# dynamic_mic_preamp.net
KiCad netlist of a schematic drawn in EAGLE
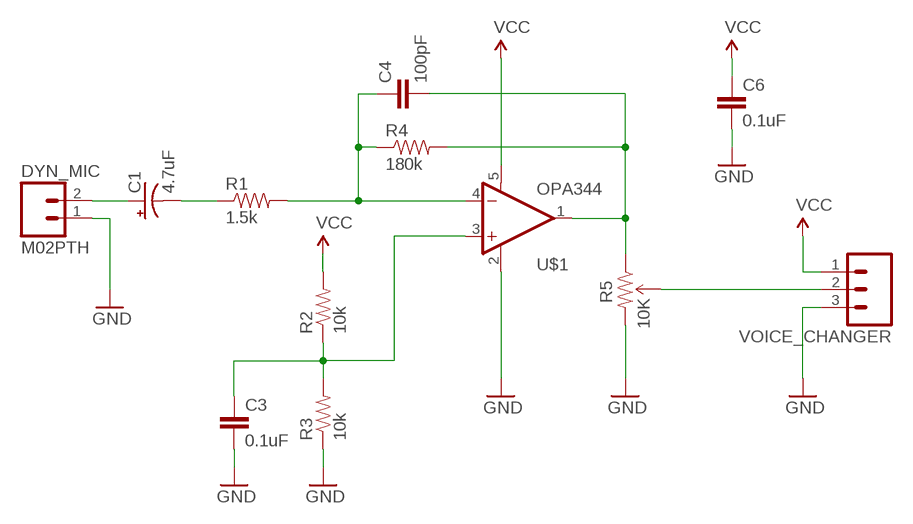
[diagram p0: schematic, sheet 1]

(export (version "E")
  (design (tool "Eeschema 10.0.6"))
  (components
    (comp (ref "C1")
      (value "4.7uF")
      (footprint "eagle-import:CPOL-RADIAL-100UF-25V")
      (libsource (lib "eagle-import") (part "CAP_POLPTH1"))
    )
    (comp (ref "C3")
      (value "0.1uF")
      (footprint "eagle-import:CAP-PTH-SMALL")
      (libsource (lib "eagle-import") (part "CAPPTH"))
    )
    (comp (ref "C4")
      (value "100pF")
      (footprint "eagle-import:CAP-PTH-SMALL")
      (libsource (lib "eagle-import") (part "CAPPTH"))
    )
    (comp (ref "C6")
      (value "0.1uF")
      (footprint "eagle-import:CAP-PTH-SMALL")
      (libsource (lib "eagle-import") (part "CAPPTH"))
    )
    (comp (ref "DYN_MIC")
      (value "M02PTH")
      (footprint "eagle-import:1X02")
      (libsource (lib "eagle-import") (part "M02PTH"))
    )
    (comp (ref "R1")
      (value "1.5k")
      (footprint "eagle-import:AXIAL-0.4")
      (libsource (lib "eagle-import") (part "RESISTORPTH-1/4W"))
    )
    (comp (ref "R2")
      (value "10k")
      (footprint "eagle-import:AXIAL-0.4")
      (libsource (lib "eagle-import") (part "RESISTORPTH-1/4W"))
    )
    (comp (ref "R3")
      (value "10k")
      (footprint "eagle-import:AXIAL-0.4")
      (libsource (lib "eagle-import") (part "RESISTORPTH-1/4W"))
    )
    (comp (ref "R4")
      (value "180k")
      (footprint "eagle-import:AXIAL-0.4")
      (libsource (lib "eagle-import") (part "RESISTORPTH-1/4W"))
    )
    (comp (ref "R5")
      (value "10K")
      (footprint "eagle-import:TRIMPOT-5MM-V2")
      (libsource (lib "eagle-import") (part "TRIMPOT"))
    )
    (comp (ref "U$1")
      (value "OPA344")
      (footprint "eagle-import:SOT23-5")
      (libsource (lib "eagle-import") (part "OPA344"))
    )
    (comp (ref "VOICE_CHANGER")
      (value "M03PTH")
      (footprint "eagle-import:1X03")
      (libsource (lib "eagle-import") (part "M03PTH"))
    )
  )
  (nets
    (net (code "1") (name "GND") (class "Default")
      (node (ref "C3") (pin "2") (pinfunction "2_2") (pintype "passive"))
      (node (ref "C6") (pin "2") (pinfunction "2_2") (pintype "passive"))
      (node (ref "DYN_MIC") (pin "1") (pinfunction "1_1") (pintype "passive"))
      (node (ref "R3") (pin "P$1") (pinfunction "1_P$1") (pintype "passive"))
      (node (ref "R5") (pin "C") (pinfunction "CW_C") (pintype "passive"))
      (node (ref "U$1") (pin "2") (pinfunction "V-_2") (pintype "power_in"))
      (node (ref "VOICE_CHANGER") (pin "3") (pinfunction "3_3") (pintype "passive"))
    )
    (net (code "2") (name "Net-(C1-+)") (class "Default")
      (node (ref "C1") (pin "1") (pinfunction "+_1") (pintype "passive"))
      (node (ref "DYN_MIC") (pin "2") (pinfunction "2_2") (pintype "passive"))
    )
    (net (code "3") (name "Net-(C1--)") (class "Default")
      (node (ref "C1") (pin "2") (pinfunction "-_2") (pintype "passive"))
      (node (ref "R1") (pin "P$1") (pinfunction "1_P$1") (pintype "passive"))
    )
    (net (code "4") (name "Net-(R1-2)") (class "Default")
      (node (ref "C4") (pin "1") (pinfunction "1_1") (pintype "passive"))
      (node (ref "R1") (pin "P$2") (pinfunction "2_P$2") (pintype "passive"))
      (node (ref "R4") (pin "P$1") (pinfunction "1_P$1") (pintype "passive"))
      (node (ref "U$1") (pin "4") (pinfunction "-IN_4") (pintype "input"))
    )
    (net (code "5") (name "Net-(R2-1)") (class "Default")
      (node (ref "C3") (pin "1") (pinfunction "1_1") (pintype "passive"))
      (node (ref "R2") (pin "P$1") (pinfunction "1_P$1") (pintype "passive"))
      (node (ref "R3") (pin "P$2") (pinfunction "2_P$2") (pintype "passive"))
      (node (ref "U$1") (pin "3") (pinfunction "+IN_3") (pintype "input"))
    )
    (net (code "6") (name "Net-(R4-2)") (class "Default")
      (node (ref "C4") (pin "2") (pinfunction "2_2") (pintype "passive"))
      (node (ref "R4") (pin "P$2") (pinfunction "2_P$2") (pintype "passive"))
      (node (ref "R5") (pin "A") (pinfunction "CCW_A") (pintype "passive"))
      (node (ref "U$1") (pin "1") (pinfunction "OUT_1") (pintype "output"))
    )
    (net (code "7") (name "Net-(R5-WIPER)") (class "Default")
      (node (ref "R5") (pin "B") (pinfunction "WIPER_B") (pintype "passive"))
      (node (ref "VOICE_CHANGER") (pin "2") (pinfunction "2_2") (pintype "passive"))
    )
    (net (code "8") (name "VCC") (class "Default")
      (node (ref "C6") (pin "1") (pinfunction "1_1") (pintype "passive"))
      (node (ref "R2") (pin "P$2") (pinfunction "2_P$2") (pintype "passive"))
      (node (ref "U$1") (pin "5") (pinfunction "V+_5") (pintype "power_in"))
      (node (ref "VOICE_CHANGER") (pin "1") (pinfunction "1_1") (pintype "passive"))
    )
  )
)
